# programmer-schematic.net
KiCad netlist of a schematic drawn in EAGLE
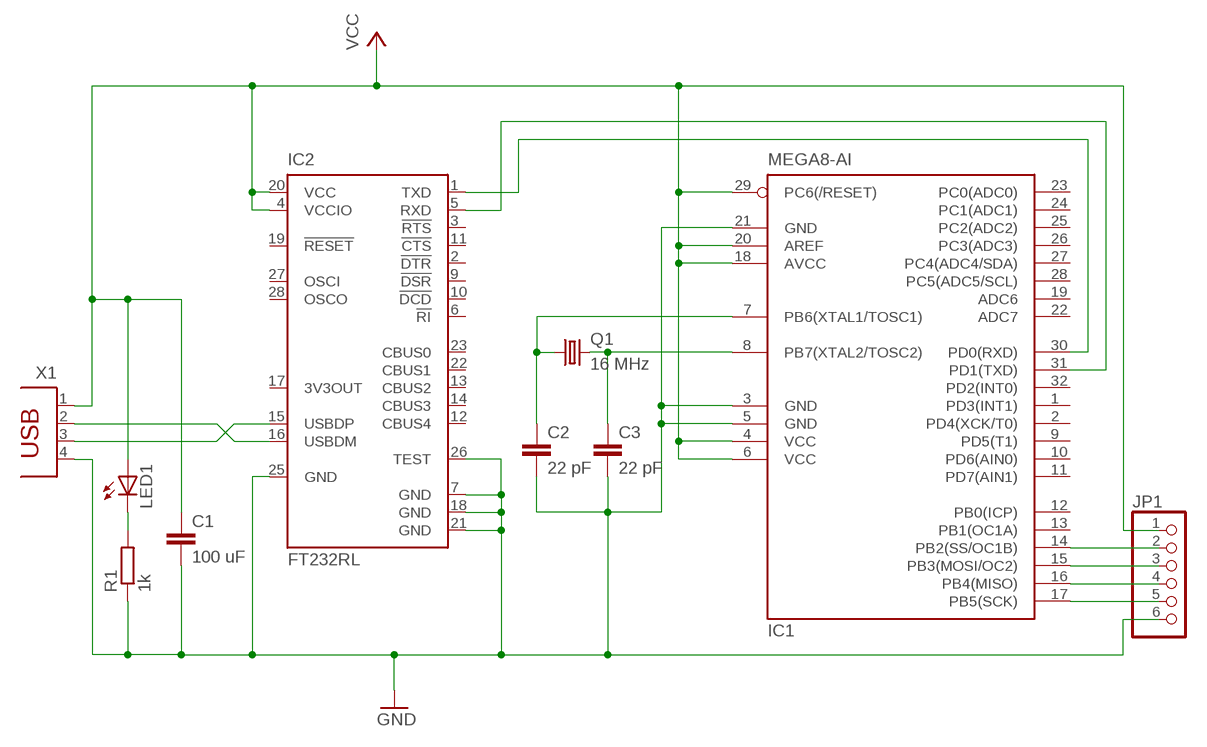
[diagram p0: schematic, sheet 1]

(export (version "E")
  (design (tool "Eeschema 10.0.6"))
  (components
    (comp (ref "C1")
      (value "100 uF")
      (footprint "eagle-import:C0805K")
      (libsource (lib "eagle-import") (part "C-EUC0805K"))
    )
    (comp (ref "C2")
      (value "22 pF")
      (footprint "eagle-import:C0805K")
      (libsource (lib "eagle-import") (part "C-EUC0805K"))
    )
    (comp (ref "C3")
      (value "22 pF")
      (footprint "eagle-import:C0805K")
      (libsource (lib "eagle-import") (part "C-EUC0805K"))
    )
    (comp (ref "IC1")
      (value "MEGA8-AI")
      (footprint "eagle-import:TQFP32-08")
      (fields (field (name "MPN") "ATMEGA8-16AU"))
      (libsource (lib "eagle-import") (part "MEGA8-AI"))
    )
    (comp (ref "IC2")
      (value "FT232RL")
      (footprint "eagle-import:SSOP28")
      (libsource (lib "eagle-import") (part "FT232RL"))
    )
    (comp (ref "JP1")
      (value "PINHD-1X6/90")
      (footprint "eagle-import:1X06_90")
      (libsource (lib "eagle-import") (part "PINHD-1X6/90"))
    )
    (comp (ref "LED1")
      (value "LEDSML1206")
      (footprint "eagle-import:SML1206")
      (libsource (lib "eagle-import") (part "LEDSML1206"))
    )
    (comp (ref "Q1")
      (value "16 MHz")
      (footprint "eagle-import:SM49")
      (libsource (lib "eagle-import") (part "CRYSTALSM49"))
    )
    (comp (ref "R1")
      (value "1k")
      (footprint "eagle-import:R1206")
      (libsource (lib "eagle-import") (part "R-EU_R1206"))
    )
    (comp (ref "X1")
      (value "PN87520")
      (footprint "eagle-import:PN87520")
      (libsource (lib "eagle-import") (part "PN87520"))
    )
  )
  (nets
    (net (code "1") (name "GND") (class "Default")
      (node (ref "C1") (pin "2") (pinfunction "2_2") (pintype "passive"))
      (node (ref "C2") (pin "2") (pinfunction "2_2") (pintype "passive"))
      (node (ref "C3") (pin "2") (pinfunction "2_2") (pintype "passive"))
      (node (ref "IC1") (pin "21") (pinfunction "GND_21") (pintype "power_in"))
      (node (ref "IC1") (pin "3") (pinfunction "GND_3") (pintype "power_in"))
      (node (ref "IC1") (pin "5") (pinfunction "GND_5") (pintype "power_in"))
      (node (ref "IC2") (pin "18") (pinfunction "GND_18") (pintype "power_in"))
      (node (ref "IC2") (pin "21") (pinfunction "GND_21") (pintype "power_in"))
      (node (ref "IC2") (pin "25") (pinfunction "GND_25") (pintype "power_in"))
      (node (ref "IC2") (pin "26") (pinfunction "TEST_26") (pintype "input"))
      (node (ref "IC2") (pin "7") (pinfunction "GND_7") (pintype "power_in"))
      (node (ref "JP1") (pin "6") (pinfunction "6_6") (pintype "passive"))
      (node (ref "R1") (pin "1") (pinfunction "1_1") (pintype "passive"))
      (node (ref "X1") (pin "4") (pinfunction "4_4") (pintype "passive"))
    )
    (net (code "2") (name "Net-(IC1-PB2(SS{slash}OC1B))") (class "Default")
      (node (ref "IC1") (pin "14") (pinfunction "PB2(SS/OC1B)_14") (pintype "bidirectional"))
      (node (ref "JP1") (pin "2") (pinfunction "2_2") (pintype "passive"))
    )
    (net (code "3") (name "Net-(IC1-PB3(MOSI{slash}OC2))") (class "Default")
      (node (ref "IC1") (pin "15") (pinfunction "PB3(MOSI/OC2)_15") (pintype "bidirectional"))
      (node (ref "JP1") (pin "3") (pinfunction "3_3") (pintype "passive"))
    )
    (net (code "4") (name "Net-(IC1-PB4(MISO))") (class "Default")
      (node (ref "IC1") (pin "16") (pinfunction "PB4(MISO)_16") (pintype "bidirectional"))
      (node (ref "JP1") (pin "4") (pinfunction "4_4") (pintype "passive"))
    )
    (net (code "5") (name "Net-(IC1-PB5(SCK))") (class "Default")
      (node (ref "IC1") (pin "17") (pinfunction "PB5(SCK)_17") (pintype "bidirectional"))
      (node (ref "JP1") (pin "5") (pinfunction "5_5") (pintype "passive"))
    )
    (net (code "6") (name "Net-(IC1-PB6(XTAL1{slash}TOSC1))") (class "Default")
      (node (ref "C2") (pin "1") (pinfunction "1_1") (pintype "passive"))
      (node (ref "IC1") (pin "7") (pinfunction "PB6(XTAL1/TOSC1)_7") (pintype "bidirectional"))
      (node (ref "Q1") (pin "1") (pinfunction "1_1") (pintype "passive"))
    )
    (net (code "7") (name "Net-(IC1-PB7(XTAL2{slash}TOSC2))") (class "Default")
      (node (ref "C3") (pin "1") (pinfunction "1_1") (pintype "passive"))
      (node (ref "IC1") (pin "8") (pinfunction "PB7(XTAL2/TOSC2)_8") (pintype "bidirectional"))
      (node (ref "Q1") (pin "2") (pinfunction "2_2") (pintype "passive"))
    )
    (net (code "8") (name "Net-(IC1-PD0(RXD))") (class "Default")
      (node (ref "IC1") (pin "30") (pinfunction "PD0(RXD)_30") (pintype "bidirectional"))
      (node (ref "IC2") (pin "1") (pinfunction "TXD_1") (pintype "output"))
    )
    (net (code "9") (name "Net-(IC1-PD1(TXD))") (class "Default")
      (node (ref "IC1") (pin "31") (pinfunction "PD1(TXD)_31") (pintype "bidirectional"))
      (node (ref "IC2") (pin "5") (pinfunction "RXD_5") (pintype "input"))
    )
    (net (code "10") (name "Net-(IC2-USBDM)") (class "Default")
      (node (ref "IC2") (pin "16") (pinfunction "USBDM_16") (pintype "bidirectional"))
      (node (ref "X1") (pin "2") (pinfunction "2_2") (pintype "passive"))
    )
    (net (code "11") (name "Net-(IC2-USBDP)") (class "Default")
      (node (ref "IC2") (pin "15") (pinfunction "USBDP_15") (pintype "bidirectional"))
      (node (ref "X1") (pin "3") (pinfunction "3_3") (pintype "passive"))
    )
    (net (code "12") (name "Net-(LED1-PadC)") (class "Default")
      (node (ref "LED1") (pin "C") (pinfunction "C_C") (pintype "passive"))
      (node (ref "R1") (pin "2") (pinfunction "2_2") (pintype "passive"))
    )
    (net (code "13") (name "VCC") (class "Default")
      (node (ref "C1") (pin "1") (pinfunction "1_1") (pintype "passive"))
      (node (ref "IC1") (pin "18") (pinfunction "AVCC_18") (pintype "power_in"))
      (node (ref "IC1") (pin "20") (pinfunction "AREF_20") (pintype "passive"))
      (node (ref "IC1") (pin "29") (pinfunction "PC6(/RESET)_29") (pintype "bidirectional"))
      (node (ref "IC1") (pin "4") (pinfunction "VCC_4") (pintype "power_in"))
      (node (ref "IC1") (pin "6") (pinfunction "VCC_6") (pintype "power_in"))
      (node (ref "IC2") (pin "20") (pinfunction "VCC_20") (pintype "power_in"))
      (node (ref "IC2") (pin "4") (pinfunction "VCCIO_4") (pintype "power_in"))
      (node (ref "JP1") (pin "1") (pinfunction "1_1") (pintype "passive"))
      (node (ref "LED1") (pin "A") (pinfunction "A_A") (pintype "passive"))
      (node (ref "X1") (pin "1") (pinfunction "1_1") (pintype "passive"))
    )
    (net (code "14") (name "unconnected-(IC1-ADC6-Pad19)") (class "Default")
      (node (ref "IC1") (pin "19") (pinfunction "ADC6_19") (pintype "bidirectional"))
    )
    (net (code "15") (name "unconnected-(IC1-ADC7-Pad22)") (class "Default")
      (node (ref "IC1") (pin "22") (pinfunction "ADC7_22") (pintype "bidirectional"))
    )
    (net (code "16") (name "unconnected-(IC1-PB0(ICP)-Pad12)") (class "Default")
      (node (ref "IC1") (pin "12") (pinfunction "PB0(ICP)_12") (pintype "bidirectional"))
    )
    (net (code "17") (name "unconnected-(IC1-PB1(OC1A)-Pad13)") (class "Default")
      (node (ref "IC1") (pin "13") (pinfunction "PB1(OC1A)_13") (pintype "bidirectional"))
    )
    (net (code "18") (name "unconnected-(IC1-PC0(ADC0)-Pad23)") (class "Default")
      (node (ref "IC1") (pin "23") (pinfunction "PC0(ADC0)_23") (pintype "bidirectional"))
    )
    (net (code "19") (name "unconnected-(IC1-PC1(ADC1)-Pad24)") (class "Default")
      (node (ref "IC1") (pin "24") (pinfunction "PC1(ADC1)_24") (pintype "bidirectional"))
    )
    (net (code "20") (name "unconnected-(IC1-PC2(ADC2)-Pad25)") (class "Default")
      (node (ref "IC1") (pin "25") (pinfunction "PC2(ADC2)_25") (pintype "bidirectional"))
    )
    (net (code "21") (name "unconnected-(IC1-PC3(ADC3)-Pad26)") (class "Default")
      (node (ref "IC1") (pin "26") (pinfunction "PC3(ADC3)_26") (pintype "bidirectional"))
    )
    (net (code "22") (name "unconnected-(IC1-PC4(ADC4{slash}SDA)-Pad27)") (class "Default")
      (node (ref "IC1") (pin "27") (pinfunction "PC4(ADC4/SDA)_27") (pintype "bidirectional"))
    )
    (net (code "23") (name "unconnected-(IC1-PC5(ADC5{slash}SCL)-Pad28)") (class "Default")
      (node (ref "IC1") (pin "28") (pinfunction "PC5(ADC5/SCL)_28") (pintype "bidirectional"))
    )
    (net (code "24") (name "unconnected-(IC1-PD2(INT0)-Pad32)") (class "Default")
      (node (ref "IC1") (pin "32") (pinfunction "PD2(INT0)_32") (pintype "bidirectional"))
    )
    (net (code "25") (name "unconnected-(IC1-PD3(INT1)-Pad1)") (class "Default")
      (node (ref "IC1") (pin "1") (pinfunction "PD3(INT1)_1") (pintype "bidirectional"))
    )
    (net (code "26") (name "unconnected-(IC1-PD4(XCK{slash}T0)-Pad2)") (class "Default")
      (node (ref "IC1") (pin "2") (pinfunction "PD4(XCK/T0)_2") (pintype "bidirectional"))
    )
    (net (code "27") (name "unconnected-(IC1-PD5(T1)-Pad9)") (class "Default")
      (node (ref "IC1") (pin "9") (pinfunction "PD5(T1)_9") (pintype "bidirectional"))
    )
    (net (code "28") (name "unconnected-(IC1-PD6(AIN0)-Pad10)") (class "Default")
      (node (ref "IC1") (pin "10") (pinfunction "PD6(AIN0)_10") (pintype "bidirectional"))
    )
    (net (code "29") (name "unconnected-(IC1-PD7(AIN1)-Pad11)") (class "Default")
      (node (ref "IC1") (pin "11") (pinfunction "PD7(AIN1)_11") (pintype "bidirectional"))
    )
    (net (code "30") (name "unconnected-(IC2-3V3OUT-Pad17)") (class "Default")
      (node (ref "IC2") (pin "17") (pinfunction "3V3OUT_17") (pintype "output"))
    )
    (net (code "31") (name "unconnected-(IC2-CBUS0-Pad23)") (class "Default")
      (node (ref "IC2") (pin "23") (pinfunction "CBUS0_23") (pintype "bidirectional"))
    )
    (net (code "32") (name "unconnected-(IC2-CBUS1-Pad22)") (class "Default")
      (node (ref "IC2") (pin "22") (pinfunction "CBUS1_22") (pintype "bidirectional"))
    )
    (net (code "33") (name "unconnected-(IC2-CBUS2-Pad13)") (class "Default")
      (node (ref "IC2") (pin "13") (pinfunction "CBUS2_13") (pintype "bidirectional"))
    )
    (net (code "34") (name "unconnected-(IC2-CBUS3-Pad14)") (class "Default")
      (node (ref "IC2") (pin "14") (pinfunction "CBUS3_14") (pintype "bidirectional"))
    )
    (net (code "35") (name "unconnected-(IC2-CBUS4-Pad12)") (class "Default")
      (node (ref "IC2") (pin "12") (pinfunction "CBUS4_12") (pintype "bidirectional"))
    )
    (net (code "36") (name "unconnected-(IC2-OSCI-Pad27)") (class "Default")
      (node (ref "IC2") (pin "27") (pinfunction "OSCI_27") (pintype "input"))
    )
    (net (code "37") (name "unconnected-(IC2-OSCO-Pad28)") (class "Default")
      (node (ref "IC2") (pin "28") (pinfunction "OSCO_28") (pintype "output"))
    )
    (net (code "38") (name "unconnected-(IC2-~{CTS}-Pad11)") (class "Default")
      (node (ref "IC2") (pin "11") (pinfunction "~{CTS}_11") (pintype "input"))
    )
    (net (code "39") (name "unconnected-(IC2-~{DCD}-Pad10)") (class "Default")
      (node (ref "IC2") (pin "10") (pinfunction "~{DCD}_10") (pintype "input"))
    )
    (net (code "40") (name "unconnected-(IC2-~{DSR}-Pad9)") (class "Default")
      (node (ref "IC2") (pin "9") (pinfunction "~{DSR}_9") (pintype "input"))
    )
    (net (code "41") (name "unconnected-(IC2-~{DTR}-Pad2)") (class "Default")
      (node (ref "IC2") (pin "2") (pinfunction "~{DTR}_2") (pintype "output"))
    )
    (net (code "42") (name "unconnected-(IC2-~{RESET}-Pad19)") (class "Default")
      (node (ref "IC2") (pin "19") (pinfunction "~{RESET}_19") (pintype "input"))
    )
    (net (code "43") (name "unconnected-(IC2-~{RI}-Pad6)") (class "Default")
      (node (ref "IC2") (pin "6") (pinfunction "~{RI}_6") (pintype "input"))
    )
    (net (code "44") (name "unconnected-(IC2-~{RTS}-Pad3)") (class "Default")
      (node (ref "IC2") (pin "3") (pinfunction "~{RTS}_3") (pintype "output"))
    )
  )
)
